# SOCPowerSupplys.net
KiCad netlist of a schematic drawn in Altium Designer
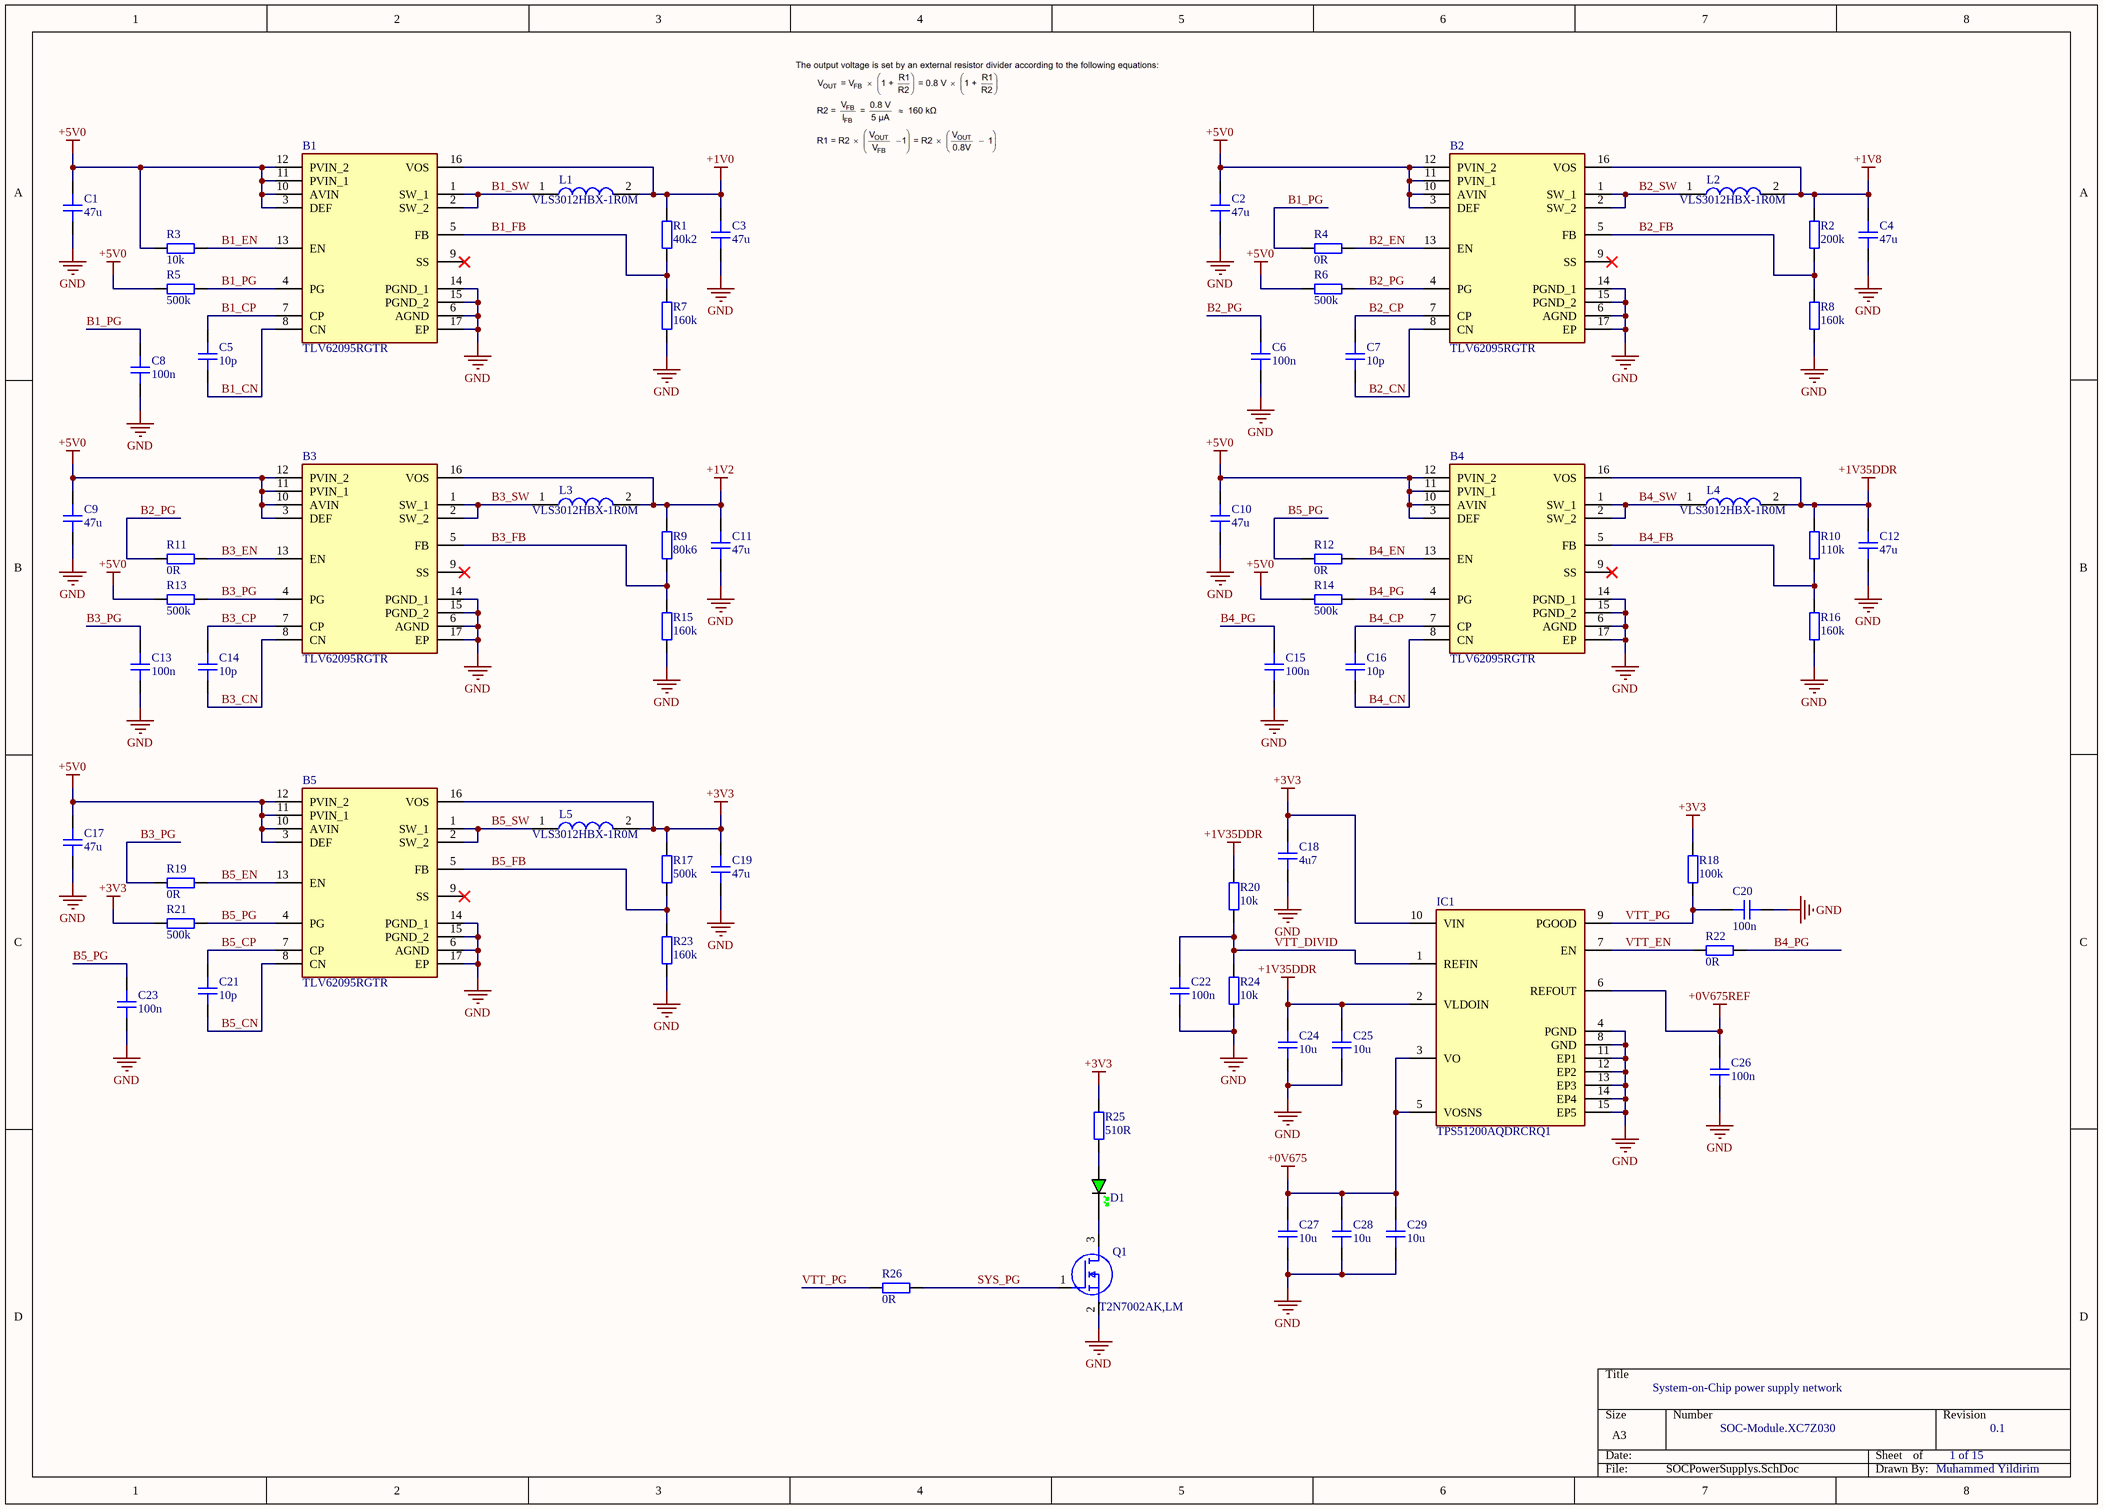
[diagram p0: SOCPowerSupplys.SchDoc]

(export (version "E")
  (design (tool "Eeschema 10.0.6"))
  (components
    (comp (ref "B1")
      (value "TLV62095RGTR")
      (footprint "QFN50P300X300X100-17N-D")
      (description "4A Synchronous Step Down Converter with DCS Control")
      (fields (field (name "MOUSER PART NUMBER") "595-TLV62095RGTR"))
      (libsource (lib "XC7Z030SCHLib") (part "TLV62095RGTR"))
    )
    (comp (ref "B2")
      (value "TLV62095RGTR")
      (footprint "QFN50P300X300X100-17N-D")
      (description "4A Synchronous Step Down Converter with DCS Control")
      (fields (field (name "MOUSER PART NUMBER") "595-TLV62095RGTR"))
      (libsource (lib "XC7Z030SCHLib") (part "TLV62095RGTR"))
    )
    (comp (ref "B3")
      (value "TLV62095RGTR")
      (footprint "QFN50P300X300X100-17N-D")
      (description "4A Synchronous Step Down Converter with DCS Control")
      (fields (field (name "MOUSER PART NUMBER") "595-TLV62095RGTR"))
      (libsource (lib "XC7Z030SCHLib") (part "TLV62095RGTR"))
    )
    (comp (ref "B4")
      (value "TLV62095RGTR")
      (footprint "QFN50P300X300X100-17N-D")
      (description "4A Synchronous Step Down Converter with DCS Control")
      (fields (field (name "MOUSER PART NUMBER") "595-TLV62095RGTR"))
      (libsource (lib "XC7Z030SCHLib") (part "TLV62095RGTR"))
    )
    (comp (ref "B5")
      (value "TLV62095RGTR")
      (footprint "QFN50P300X300X100-17N-D")
      (description "4A Synchronous Step Down Converter with DCS Control")
      (fields (field (name "MOUSER PART NUMBER") "595-TLV62095RGTR"))
      (libsource (lib "XC7Z030SCHLib") (part "TLV62095RGTR"))
    )
    (comp (ref "C1")
      (value "47u")
      (footprint "CAP_0805")
      (description "Capacitor SMD 0805")
      (libsource (lib "Schematic-Lib-PhilsLab") (part "CAP_0805"))
    )
    (comp (ref "C2")
      (value "47u")
      (footprint "CAP_0805")
      (description "Capacitor SMD 0805")
      (libsource (lib "Schematic-Lib-PhilsLab") (part "CAP_0805"))
    )
    (comp (ref "C3")
      (value "47u")
      (footprint "CAP_0805")
      (description "Capacitor SMD 0805")
      (libsource (lib "Schematic-Lib-PhilsLab") (part "CAP_0805"))
    )
    (comp (ref "C4")
      (value "47u")
      (footprint "CAP_0805")
      (description "Capacitor SMD 0805")
      (libsource (lib "Schematic-Lib-PhilsLab") (part "CAP_0805"))
    )
    (comp (ref "C5")
      (value "10p")
      (footprint "CAP_0402")
      (description "Capacitor SMD 0402")
      (libsource (lib "Schematic-Lib-PhilsLab") (part "CAP_0402"))
    )
    (comp (ref "C6")
      (value "100n")
      (footprint "CAP_0402")
      (description "Capacitor SMD 0402")
      (libsource (lib "Schematic-Lib-PhilsLab") (part "CAP_0402"))
    )
    (comp (ref "C7")
      (value "10p")
      (footprint "CAP_0402")
      (description "Capacitor SMD 0402")
      (libsource (lib "Schematic-Lib-PhilsLab") (part "CAP_0402"))
    )
    (comp (ref "C8")
      (value "100n")
      (footprint "CAP_0402")
      (description "Capacitor SMD 0402")
      (libsource (lib "Schematic-Lib-PhilsLab") (part "CAP_0402"))
    )
    (comp (ref "C9")
      (value "47u")
      (footprint "CAP_0805")
      (description "Capacitor SMD 0805")
      (libsource (lib "Schematic-Lib-PhilsLab") (part "CAP_0805"))
    )
    (comp (ref "C10")
      (value "47u")
      (footprint "CAP_0805")
      (description "Capacitor SMD 0805")
      (libsource (lib "Schematic-Lib-PhilsLab") (part "CAP_0805"))
    )
    (comp (ref "C11")
      (value "47u")
      (footprint "CAP_0805")
      (description "Capacitor SMD 0805")
      (libsource (lib "Schematic-Lib-PhilsLab") (part "CAP_0805"))
    )
    (comp (ref "C12")
      (value "47u")
      (footprint "CAP_0805")
      (description "Capacitor SMD 0805")
      (libsource (lib "Schematic-Lib-PhilsLab") (part "CAP_0805"))
    )
    (comp (ref "C13")
      (value "100n")
      (footprint "CAP_0402")
      (description "Capacitor SMD 0402")
      (libsource (lib "Schematic-Lib-PhilsLab") (part "CAP_0402"))
    )
    (comp (ref "C14")
      (value "10p")
      (footprint "CAP_0402")
      (description "Capacitor SMD 0402")
      (libsource (lib "Schematic-Lib-PhilsLab") (part "CAP_0402"))
    )
    (comp (ref "C15")
      (value "100n")
      (footprint "CAP_0402")
      (description "Capacitor SMD 0402")
      (libsource (lib "Schematic-Lib-PhilsLab") (part "CAP_0402"))
    )
    (comp (ref "C16")
      (value "10p")
      (footprint "CAP_0402")
      (description "Capacitor SMD 0402")
      (libsource (lib "Schematic-Lib-PhilsLab") (part "CAP_0402"))
    )
    (comp (ref "C17")
      (value "47u")
      (footprint "CAP_0805")
      (description "Capacitor SMD 0805")
      (libsource (lib "Schematic-Lib-PhilsLab") (part "CAP_0805"))
    )
    (comp (ref "C18")
      (value "4u7")
      (footprint "CAP_0402")
      (description "Capacitor SMD 0402")
      (libsource (lib "Schematic-Lib-PhilsLab") (part "CAP_0402"))
    )
    (comp (ref "C19")
      (value "47u")
      (footprint "CAP_0805")
      (description "Capacitor SMD 0805")
      (libsource (lib "Schematic-Lib-PhilsLab") (part "CAP_0805"))
    )
    (comp (ref "C20")
      (value "100n")
      (footprint "CAP_0402")
      (description "Capacitor SMD 0402")
      (libsource (lib "Schematic-Lib-PhilsLab") (part "CAP_0402"))
    )
    (comp (ref "C21")
      (value "10p")
      (footprint "CAP_0402")
      (description "Capacitor SMD 0402")
      (libsource (lib "Schematic-Lib-PhilsLab") (part "CAP_0402"))
    )
    (comp (ref "C22")
      (value "100n")
      (footprint "CAP_0402")
      (description "Capacitor SMD 0402")
      (libsource (lib "Schematic-Lib-PhilsLab") (part "CAP_0402"))
    )
    (comp (ref "C23")
      (value "100n")
      (footprint "CAP_0402")
      (description "Capacitor SMD 0402")
      (libsource (lib "Schematic-Lib-PhilsLab") (part "CAP_0402"))
    )
    (comp (ref "C24")
      (value "10u")
      (footprint "CAP_0603")
      (description "Capacitor SMD 0603")
      (libsource (lib "Schematic-Lib-PhilsLab") (part "CAP_0603"))
    )
    (comp (ref "C25")
      (value "10u")
      (footprint "CAP_0603")
      (description "Capacitor SMD 0603")
      (libsource (lib "Schematic-Lib-PhilsLab") (part "CAP_0603"))
    )
    (comp (ref "C26")
      (value "100n")
      (footprint "CAP_0402")
      (description "Capacitor SMD 0402")
      (libsource (lib "Schematic-Lib-PhilsLab") (part "CAP_0402"))
    )
    (comp (ref "C27")
      (value "10u")
      (footprint "CAP_0603")
      (description "Capacitor SMD 0603")
      (libsource (lib "Schematic-Lib-PhilsLab") (part "CAP_0603"))
    )
    (comp (ref "C28")
      (value "10u")
      (footprint "CAP_0603")
      (description "Capacitor SMD 0603")
      (libsource (lib "Schematic-Lib-PhilsLab") (part "CAP_0603"))
    )
    (comp (ref "C29")
      (value "10u")
      (footprint "CAP_0603")
      (description "Capacitor SMD 0603")
      (libsource (lib "Schematic-Lib-PhilsLab") (part "CAP_0603"))
    )
    (comp (ref "D1")
      (value "GREEN")
      (footprint "LED_0603_GREEN")
      (description "LED 0603 GREEN SMD")
      (libsource (lib "Schematic-Lib-PhilsLab") (part "LED_0603_GREEN"))
    )
    (comp (ref "IC1")
      (value "TPS51200AQDRCRQ1")
      (footprint "TPS51200AQDRCRQ1")
      (description "Texas Instruments Sink and Source DDR Termination Regulator")
      (libsource (lib "XC7Z030SCHLib") (part "TPS51200AQDRCRQ1"))
    )
    (comp (ref "L1")
      (value "VLS3012HBX-1R0M")
      (footprint "XC7Z030PCBLib:VLS3012")
      (description "Inductor")
      (fields (field (name "MOUSER PART NUMBER") "810-VLS3012HBX-1R0M"))
      (libsource (lib "XC7Z030SCHLib") (part "VLS3012HBX-1R0M"))
    )
    (comp (ref "L2")
      (value "VLS3012HBX-1R0M")
      (footprint "XC7Z030PCBLib:VLS3012")
      (description "Inductor")
      (fields (field (name "MOUSER PART NUMBER") "810-VLS3012HBX-1R0M"))
      (libsource (lib "XC7Z030SCHLib") (part "VLS3012HBX-1R0M"))
    )
    (comp (ref "L3")
      (value "VLS3012HBX-1R0M")
      (footprint "XC7Z030PCBLib:VLS3012")
      (description "Inductor")
      (fields (field (name "MOUSER PART NUMBER") "810-VLS3012HBX-1R0M"))
      (libsource (lib "XC7Z030SCHLib") (part "VLS3012HBX-1R0M"))
    )
    (comp (ref "L4")
      (value "VLS3012HBX-1R0M")
      (footprint "XC7Z030PCBLib:VLS3012")
      (description "Inductor")
      (fields (field (name "MOUSER PART NUMBER") "810-VLS3012HBX-1R0M"))
      (libsource (lib "XC7Z030SCHLib") (part "VLS3012HBX-1R0M"))
    )
    (comp (ref "L5")
      (value "VLS3012HBX-1R0M")
      (footprint "XC7Z030PCBLib:VLS3012")
      (description "Inductor")
      (fields (field (name "MOUSER PART NUMBER") "810-VLS3012HBX-1R0M"))
      (libsource (lib "XC7Z030SCHLib") (part "VLS3012HBX-1R0M"))
    )
    (comp (ref "Q1")
      (value "T2N7002AK,LM")
      (footprint "Footprint-Lib-PhilsLab:TBAT54CLM")
      (description "MOSFET (N-Channel)")
      (fields (field (name "MOUSER PART NUMBER") "757-T2N7002AKLM"))
      (libsource (lib "Schematic-Lib-PhilsLab") (part "T2N7002AK,LM"))
    )
    (comp (ref "R1")
      (value "40k2")
      (footprint "RES_0402")
      (description "Resistor SMD 0402")
      (libsource (lib "Schematic-Lib-PhilsLab") (part "RES_0402"))
    )
    (comp (ref "R2")
      (value "200k")
      (footprint "RES_0402")
      (description "Resistor SMD 0402")
      (libsource (lib "Schematic-Lib-PhilsLab") (part "RES_0402"))
    )
    (comp (ref "R3")
      (value "10k")
      (footprint "RES_0402")
      (description "Resistor SMD 0402")
      (libsource (lib "Schematic-Lib-PhilsLab") (part "RES_0402"))
    )
    (comp (ref "R4")
      (value "0R")
      (footprint "RES_0402")
      (description "Resistor SMD 0402")
      (libsource (lib "Schematic-Lib-PhilsLab") (part "RES_0402"))
    )
    (comp (ref "R5")
      (value "500k")
      (footprint "RES_0402")
      (description "Resistor SMD 0402")
      (libsource (lib "Schematic-Lib-PhilsLab") (part "RES_0402"))
    )
    (comp (ref "R6")
      (value "500k")
      (footprint "RES_0402")
      (description "Resistor SMD 0402")
      (libsource (lib "Schematic-Lib-PhilsLab") (part "RES_0402"))
    )
    (comp (ref "R7")
      (value "160k")
      (footprint "RES_0402")
      (description "Resistor SMD 0402")
      (libsource (lib "Schematic-Lib-PhilsLab") (part "RES_0402"))
    )
    (comp (ref "R8")
      (value "160k")
      (footprint "RES_0402")
      (description "Resistor SMD 0402")
      (libsource (lib "Schematic-Lib-PhilsLab") (part "RES_0402"))
    )
    (comp (ref "R9")
      (value "80k6")
      (footprint "RES_0402")
      (description "Resistor SMD 0402")
      (libsource (lib "Schematic-Lib-PhilsLab") (part "RES_0402"))
    )
    (comp (ref "R10")
      (value "110k")
      (footprint "RES_0402")
      (description "Resistor SMD 0402")
      (libsource (lib "Schematic-Lib-PhilsLab") (part "RES_0402"))
    )
    (comp (ref "R11")
      (value "0R")
      (footprint "RES_0402")
      (description "Resistor SMD 0402")
      (libsource (lib "Schematic-Lib-PhilsLab") (part "RES_0402"))
    )
    (comp (ref "R12")
      (value "0R")
      (footprint "RES_0402")
      (description "Resistor SMD 0402")
      (libsource (lib "Schematic-Lib-PhilsLab") (part "RES_0402"))
    )
    (comp (ref "R13")
      (value "500k")
      (footprint "RES_0402")
      (description "Resistor SMD 0402")
      (libsource (lib "Schematic-Lib-PhilsLab") (part "RES_0402"))
    )
    (comp (ref "R14")
      (value "500k")
      (footprint "RES_0402")
      (description "Resistor SMD 0402")
      (libsource (lib "Schematic-Lib-PhilsLab") (part "RES_0402"))
    )
    (comp (ref "R15")
      (value "160k")
      (footprint "RES_0402")
      (description "Resistor SMD 0402")
      (libsource (lib "Schematic-Lib-PhilsLab") (part "RES_0402"))
    )
    (comp (ref "R16")
      (value "160k")
      (footprint "RES_0402")
      (description "Resistor SMD 0402")
      (libsource (lib "Schematic-Lib-PhilsLab") (part "RES_0402"))
    )
    (comp (ref "R17")
      (value "500k")
      (footprint "RES_0402")
      (description "Resistor SMD 0402")
      (libsource (lib "Schematic-Lib-PhilsLab") (part "RES_0402"))
    )
    (comp (ref "R18")
      (value "100k")
      (footprint "RES_0402")
      (description "Resistor SMD 0402")
      (libsource (lib "Schematic-Lib-PhilsLab") (part "RES_0402"))
    )
    (comp (ref "R19")
      (value "0R")
      (footprint "RES_0402")
      (description "Resistor SMD 0402")
      (libsource (lib "Schematic-Lib-PhilsLab") (part "RES_0402"))
    )
    (comp (ref "R20")
      (value "10k")
      (footprint "RES_0402")
      (description "Resistor SMD 0402")
      (libsource (lib "Schematic-Lib-PhilsLab") (part "RES_0402"))
    )
    (comp (ref "R21")
      (value "500k")
      (footprint "RES_0402")
      (description "Resistor SMD 0402")
      (libsource (lib "Schematic-Lib-PhilsLab") (part "RES_0402"))
    )
    (comp (ref "R22")
      (value "0R")
      (footprint "RES_0402")
      (description "Resistor SMD 0402")
      (libsource (lib "Schematic-Lib-PhilsLab") (part "RES_0402"))
    )
    (comp (ref "R23")
      (value "160k")
      (footprint "RES_0402")
      (description "Resistor SMD 0402")
      (libsource (lib "Schematic-Lib-PhilsLab") (part "RES_0402"))
    )
    (comp (ref "R24")
      (value "10k")
      (footprint "RES_0402")
      (description "Resistor SMD 0402")
      (libsource (lib "Schematic-Lib-PhilsLab") (part "RES_0402"))
    )
    (comp (ref "R25")
      (value "510R")
      (footprint "RES_0603")
      (description "Resistor SMD 0603")
      (libsource (lib "Schematic-Lib-PhilsLab") (part "RES_0603"))
    )
    (comp (ref "R26")
      (value "0R")
      (footprint "RES_0402")
      (description "Resistor SMD 0402")
      (libsource (lib "Schematic-Lib-PhilsLab") (part "RES_0402"))
    )
  )
  (nets
    (net (code "1") (name "+0V675") (class "Default")
      (node (ref "C27") (pin "2") (pinfunction "2_2") (pintype "passive"))
      (node (ref "C28") (pin "2") (pinfunction "2_2") (pintype "passive"))
      (node (ref "C29") (pin "2") (pinfunction "2_2") (pintype "passive"))
      (node (ref "IC1") (pin "3") (pinfunction "VO_3") (pintype "passive"))
      (node (ref "IC1") (pin "5") (pinfunction "VOSNS_5") (pintype "passive"))
    )
    (net (code "2") (name "+0V675REF") (class "Default")
      (node (ref "C26") (pin "2") (pinfunction "2_2") (pintype "passive"))
      (node (ref "IC1") (pin "6") (pinfunction "REFOUT_6") (pintype "passive"))
    )
    (net (code "3") (name "+1V0") (class "Default")
      (node (ref "B1") (pin "16") (pinfunction "VOS_16") (pintype "passive"))
      (node (ref "C3") (pin "2") (pinfunction "2_2") (pintype "passive"))
      (node (ref "L1") (pin "2") (pinfunction "2_2") (pintype "passive"))
      (node (ref "R1") (pin "2") (pinfunction "2_2") (pintype "passive"))
    )
    (net (code "4") (name "+1V2") (class "Default")
      (node (ref "B3") (pin "16") (pinfunction "VOS_16") (pintype "passive"))
      (node (ref "C11") (pin "2") (pinfunction "2_2") (pintype "passive"))
      (node (ref "L3") (pin "2") (pinfunction "2_2") (pintype "passive"))
      (node (ref "R9") (pin "2") (pinfunction "2_2") (pintype "passive"))
    )
    (net (code "5") (name "+1V8") (class "Default")
      (node (ref "B2") (pin "16") (pinfunction "VOS_16") (pintype "passive"))
      (node (ref "C4") (pin "2") (pinfunction "2_2") (pintype "passive"))
      (node (ref "L2") (pin "2") (pinfunction "2_2") (pintype "passive"))
      (node (ref "R2") (pin "2") (pinfunction "2_2") (pintype "passive"))
    )
    (net (code "6") (name "+1V35DDR") (class "Default")
      (node (ref "B4") (pin "16") (pinfunction "VOS_16") (pintype "passive"))
      (node (ref "C12") (pin "2") (pinfunction "2_2") (pintype "passive"))
      (node (ref "C24") (pin "2") (pinfunction "2_2") (pintype "passive"))
      (node (ref "C25") (pin "2") (pinfunction "2_2") (pintype "passive"))
      (node (ref "IC1") (pin "2") (pinfunction "VLDOIN_2") (pintype "passive"))
      (node (ref "L4") (pin "2") (pinfunction "2_2") (pintype "passive"))
      (node (ref "R10") (pin "2") (pinfunction "2_2") (pintype "passive"))
      (node (ref "R20") (pin "2") (pinfunction "2_2") (pintype "passive"))
    )
    (net (code "7") (name "+3V3") (class "Default")
      (node (ref "B5") (pin "16") (pinfunction "VOS_16") (pintype "passive"))
      (node (ref "C18") (pin "2") (pinfunction "2_2") (pintype "passive"))
      (node (ref "C19") (pin "2") (pinfunction "2_2") (pintype "passive"))
      (node (ref "IC1") (pin "10") (pinfunction "VIN_10") (pintype "passive"))
      (node (ref "L5") (pin "2") (pinfunction "2_2") (pintype "passive"))
      (node (ref "R17") (pin "2") (pinfunction "2_2") (pintype "passive"))
      (node (ref "R18") (pin "2") (pinfunction "2_2") (pintype "passive"))
      (node (ref "R21") (pin "1") (pinfunction "1_1") (pintype "passive"))
      (node (ref "R25") (pin "2") (pinfunction "2_2") (pintype "passive"))
    )
    (net (code "8") (name "+5V0") (class "Default")
      (node (ref "B1") (pin "10") (pinfunction "AVIN_10") (pintype "passive"))
      (node (ref "B1") (pin "11") (pinfunction "PVIN_1_11") (pintype "passive"))
      (node (ref "B1") (pin "12") (pinfunction "PVIN_2_12") (pintype "passive"))
      (node (ref "B1") (pin "3") (pinfunction "DEF_3") (pintype "passive"))
      (node (ref "B2") (pin "10") (pinfunction "AVIN_10") (pintype "passive"))
      (node (ref "B2") (pin "11") (pinfunction "PVIN_1_11") (pintype "passive"))
      (node (ref "B2") (pin "12") (pinfunction "PVIN_2_12") (pintype "passive"))
      (node (ref "B2") (pin "3") (pinfunction "DEF_3") (pintype "passive"))
      (node (ref "B3") (pin "10") (pinfunction "AVIN_10") (pintype "passive"))
      (node (ref "B3") (pin "11") (pinfunction "PVIN_1_11") (pintype "passive"))
      (node (ref "B3") (pin "12") (pinfunction "PVIN_2_12") (pintype "passive"))
      (node (ref "B3") (pin "3") (pinfunction "DEF_3") (pintype "passive"))
      (node (ref "B4") (pin "10") (pinfunction "AVIN_10") (pintype "passive"))
      (node (ref "B4") (pin "11") (pinfunction "PVIN_1_11") (pintype "passive"))
      (node (ref "B4") (pin "12") (pinfunction "PVIN_2_12") (pintype "passive"))
      (node (ref "B4") (pin "3") (pinfunction "DEF_3") (pintype "passive"))
      (node (ref "B5") (pin "10") (pinfunction "AVIN_10") (pintype "passive"))
      (node (ref "B5") (pin "11") (pinfunction "PVIN_1_11") (pintype "passive"))
      (node (ref "B5") (pin "12") (pinfunction "PVIN_2_12") (pintype "passive"))
      (node (ref "B5") (pin "3") (pinfunction "DEF_3") (pintype "passive"))
      (node (ref "C1") (pin "2") (pinfunction "2_2") (pintype "passive"))
      (node (ref "C10") (pin "2") (pinfunction "2_2") (pintype "passive"))
      (node (ref "C17") (pin "2") (pinfunction "2_2") (pintype "passive"))
      (node (ref "C2") (pin "2") (pinfunction "2_2") (pintype "passive"))
      (node (ref "C9") (pin "2") (pinfunction "2_2") (pintype "passive"))
      (node (ref "R13") (pin "1") (pinfunction "1_1") (pintype "passive"))
      (node (ref "R14") (pin "1") (pinfunction "1_1") (pintype "passive"))
      (node (ref "R3") (pin "1") (pinfunction "1_1") (pintype "passive"))
      (node (ref "R5") (pin "1") (pinfunction "1_1") (pintype "passive"))
      (node (ref "R6") (pin "1") (pinfunction "1_1") (pintype "passive"))
    )
    (net (code "9") (name "/B1_CN") (class "Default")
      (node (ref "B1") (pin "8") (pinfunction "CN_8") (pintype "passive"))
      (node (ref "C5") (pin "1") (pinfunction "1_1") (pintype "passive"))
    )
    (net (code "10") (name "/B1_CP") (class "Default")
      (node (ref "B1") (pin "7") (pinfunction "CP_7") (pintype "passive"))
      (node (ref "C5") (pin "2") (pinfunction "2_2") (pintype "passive"))
    )
    (net (code "11") (name "/B1_EN") (class "Default")
      (node (ref "B1") (pin "13") (pinfunction "EN_13") (pintype "passive"))
      (node (ref "R3") (pin "2") (pinfunction "2_2") (pintype "passive"))
    )
    (net (code "12") (name "/B1_FB") (class "Default")
      (node (ref "B1") (pin "5") (pinfunction "FB_5") (pintype "passive"))
      (node (ref "R1") (pin "1") (pinfunction "1_1") (pintype "passive"))
      (node (ref "R7") (pin "2") (pinfunction "2_2") (pintype "passive"))
    )
    (net (code "13") (name "/B1_PG") (class "Default")
      (node (ref "B1") (pin "4") (pinfunction "PG_4") (pintype "passive"))
      (node (ref "C8") (pin "2") (pinfunction "2_2") (pintype "passive"))
      (node (ref "R4") (pin "2") (pinfunction "2_2") (pintype "passive"))
      (node (ref "R5") (pin "2") (pinfunction "2_2") (pintype "passive"))
    )
    (net (code "14") (name "/B1_SW") (class "Default")
      (node (ref "B1") (pin "1") (pinfunction "SW_1_1") (pintype "passive"))
      (node (ref "B1") (pin "2") (pinfunction "SW_2_2") (pintype "passive"))
      (node (ref "L1") (pin "1") (pinfunction "1_1") (pintype "passive"))
    )
    (net (code "15") (name "/B2_CN") (class "Default")
      (node (ref "B2") (pin "8") (pinfunction "CN_8") (pintype "passive"))
      (node (ref "C7") (pin "1") (pinfunction "1_1") (pintype "passive"))
    )
    (net (code "16") (name "/B2_CP") (class "Default")
      (node (ref "B2") (pin "7") (pinfunction "CP_7") (pintype "passive"))
      (node (ref "C7") (pin "2") (pinfunction "2_2") (pintype "passive"))
    )
    (net (code "17") (name "/B2_EN") (class "Default")
      (node (ref "B2") (pin "13") (pinfunction "EN_13") (pintype "passive"))
      (node (ref "R4") (pin "1") (pinfunction "1_1") (pintype "passive"))
    )
    (net (code "18") (name "/B2_FB") (class "Default")
      (node (ref "B2") (pin "5") (pinfunction "FB_5") (pintype "passive"))
      (node (ref "R2") (pin "1") (pinfunction "1_1") (pintype "passive"))
      (node (ref "R8") (pin "2") (pinfunction "2_2") (pintype "passive"))
    )
    (net (code "19") (name "/B2_PG") (class "Default")
      (node (ref "B2") (pin "4") (pinfunction "PG_4") (pintype "passive"))
      (node (ref "C6") (pin "2") (pinfunction "2_2") (pintype "passive"))
      (node (ref "R11") (pin "2") (pinfunction "2_2") (pintype "passive"))
      (node (ref "R6") (pin "2") (pinfunction "2_2") (pintype "passive"))
    )
    (net (code "20") (name "/B2_SW") (class "Default")
      (node (ref "B2") (pin "1") (pinfunction "SW_1_1") (pintype "passive"))
      (node (ref "B2") (pin "2") (pinfunction "SW_2_2") (pintype "passive"))
      (node (ref "L2") (pin "1") (pinfunction "1_1") (pintype "passive"))
    )
    (net (code "21") (name "/B3_CN") (class "Default")
      (node (ref "B3") (pin "8") (pinfunction "CN_8") (pintype "passive"))
      (node (ref "C14") (pin "1") (pinfunction "1_1") (pintype "passive"))
    )
    (net (code "22") (name "/B3_CP") (class "Default")
      (node (ref "B3") (pin "7") (pinfunction "CP_7") (pintype "passive"))
      (node (ref "C14") (pin "2") (pinfunction "2_2") (pintype "passive"))
    )
    (net (code "23") (name "/B3_EN") (class "Default")
      (node (ref "B3") (pin "13") (pinfunction "EN_13") (pintype "passive"))
      (node (ref "R11") (pin "1") (pinfunction "1_1") (pintype "passive"))
    )
    (net (code "24") (name "/B3_FB") (class "Default")
      (node (ref "B3") (pin "5") (pinfunction "FB_5") (pintype "passive"))
      (node (ref "R15") (pin "2") (pinfunction "2_2") (pintype "passive"))
      (node (ref "R9") (pin "1") (pinfunction "1_1") (pintype "passive"))
    )
    (net (code "25") (name "/B3_PG") (class "Default")
      (node (ref "B3") (pin "4") (pinfunction "PG_4") (pintype "passive"))
      (node (ref "C13") (pin "2") (pinfunction "2_2") (pintype "passive"))
      (node (ref "R13") (pin "2") (pinfunction "2_2") (pintype "passive"))
      (node (ref "R19") (pin "2") (pinfunction "2_2") (pintype "passive"))
    )
    (net (code "26") (name "/B3_SW") (class "Default")
      (node (ref "B3") (pin "1") (pinfunction "SW_1_1") (pintype "passive"))
      (node (ref "B3") (pin "2") (pinfunction "SW_2_2") (pintype "passive"))
      (node (ref "L3") (pin "1") (pinfunction "1_1") (pintype "passive"))
    )
    (net (code "27") (name "/B4_CN") (class "Default")
      (node (ref "B4") (pin "8") (pinfunction "CN_8") (pintype "passive"))
      (node (ref "C16") (pin "1") (pinfunction "1_1") (pintype "passive"))
    )
    (net (code "28") (name "/B4_CP") (class "Default")
      (node (ref "B4") (pin "7") (pinfunction "CP_7") (pintype "passive"))
      (node (ref "C16") (pin "2") (pinfunction "2_2") (pintype "passive"))
    )
    (net (code "29") (name "/B4_EN") (class "Default")
      (node (ref "B4") (pin "13") (pinfunction "EN_13") (pintype "passive"))
      (node (ref "R12") (pin "1") (pinfunction "1_1") (pintype "passive"))
    )
    (net (code "30") (name "/B4_FB") (class "Default")
      (node (ref "B4") (pin "5") (pinfunction "FB_5") (pintype "passive"))
      (node (ref "R10") (pin "1") (pinfunction "1_1") (pintype "passive"))
      (node (ref "R16") (pin "2") (pinfunction "2_2") (pintype "passive"))
    )
    (net (code "31") (name "/B4_PG") (class "Default")
      (node (ref "B4") (pin "4") (pinfunction "PG_4") (pintype "passive"))
      (node (ref "C15") (pin "2") (pinfunction "2_2") (pintype "passive"))
      (node (ref "R14") (pin "2") (pinfunction "2_2") (pintype "passive"))
      (node (ref "R22") (pin "1") (pinfunction "1_1") (pintype "passive"))
    )
    (net (code "32") (name "/B4_SW") (class "Default")
      (node (ref "B4") (pin "1") (pinfunction "SW_1_1") (pintype "passive"))
      (node (ref "B4") (pin "2") (pinfunction "SW_2_2") (pintype "passive"))
      (node (ref "L4") (pin "1") (pinfunction "1_1") (pintype "passive"))
    )
    (net (code "33") (name "/B5_CN") (class "Default")
      (node (ref "B5") (pin "8") (pinfunction "CN_8") (pintype "passive"))
      (node (ref "C21") (pin "1") (pinfunction "1_1") (pintype "passive"))
    )
    (net (code "34") (name "/B5_CP") (class "Default")
      (node (ref "B5") (pin "7") (pinfunction "CP_7") (pintype "passive"))
      (node (ref "C21") (pin "2") (pinfunction "2_2") (pintype "passive"))
    )
    (net (code "35") (name "/B5_EN") (class "Default")
      (node (ref "B5") (pin "13") (pinfunction "EN_13") (pintype "passive"))
      (node (ref "R19") (pin "1") (pinfunction "1_1") (pintype "passive"))
    )
    (net (code "36") (name "/B5_FB") (class "Default")
      (node (ref "B5") (pin "5") (pinfunction "FB_5") (pintype "passive"))
      (node (ref "R17") (pin "1") (pinfunction "1_1") (pintype "passive"))
      (node (ref "R23") (pin "2") (pinfunction "2_2") (pintype "passive"))
    )
    (net (code "37") (name "/B5_PG") (class "Default")
      (node (ref "B5") (pin "4") (pinfunction "PG_4") (pintype "passive"))
      (node (ref "C23") (pin "2") (pinfunction "2_2") (pintype "passive"))
      (node (ref "R12") (pin "2") (pinfunction "2_2") (pintype "passive"))
      (node (ref "R21") (pin "2") (pinfunction "2_2") (pintype "passive"))
    )
    (net (code "38") (name "/B5_SW") (class "Default")
      (node (ref "B5") (pin "1") (pinfunction "SW_1_1") (pintype "passive"))
      (node (ref "B5") (pin "2") (pinfunction "SW_2_2") (pintype "passive"))
      (node (ref "L5") (pin "1") (pinfunction "1_1") (pintype "passive"))
    )
    (net (code "39") (name "/SYS_PG") (class "Default")
      (node (ref "Q1") (pin "1") (pinfunction "G_1") (pintype "passive"))
      (node (ref "R26") (pin "1") (pinfunction "1_1") (pintype "passive"))
    )
    (net (code "40") (name "/VTT_DIVID") (class "Default")
      (node (ref "C22") (pin "2") (pinfunction "2_2") (pintype "passive"))
      (node (ref "IC1") (pin "1") (pinfunction "REFIN_1") (pintype "passive"))
      (node (ref "R20") (pin "1") (pinfunction "1_1") (pintype "passive"))
      (node (ref "R24") (pin "2") (pinfunction "2_2") (pintype "passive"))
    )
    (net (code "41") (name "/VTT_EN") (class "Default")
      (node (ref "IC1") (pin "7") (pinfunction "EN_7") (pintype "passive"))
      (node (ref "R22") (pin "2") (pinfunction "2_2") (pintype "passive"))
    )
    (net (code "42") (name "/VTT_PG") (class "Default")
      (node (ref "C20") (pin "2") (pinfunction "2_2") (pintype "passive"))
      (node (ref "IC1") (pin "9") (pinfunction "PGOOD_9") (pintype "passive"))
      (node (ref "R18") (pin "1") (pinfunction "1_1") (pintype "passive"))
      (node (ref "R26") (pin "2") (pinfunction "2_2") (pintype "passive"))
    )
    (net (code "43") (name "GND") (class "Default")
      (node (ref "B1") (pin "14") (pinfunction "PGND_1_14") (pintype "passive"))
      (node (ref "B1") (pin "15") (pinfunction "PGND_2_15") (pintype "passive"))
      (node (ref "B1") (pin "17") (pinfunction "EP_17") (pintype "passive"))
      (node (ref "B1") (pin "6") (pinfunction "AGND_6") (pintype "passive"))
      (node (ref "B2") (pin "14") (pinfunction "PGND_1_14") (pintype "passive"))
      (node (ref "B2") (pin "15") (pinfunction "PGND_2_15") (pintype "passive"))
      (node (ref "B2") (pin "17") (pinfunction "EP_17") (pintype "passive"))
      (node (ref "B2") (pin "6") (pinfunction "AGND_6") (pintype "passive"))
      (node (ref "B3") (pin "14") (pinfunction "PGND_1_14") (pintype "passive"))
      (node (ref "B3") (pin "15") (pinfunction "PGND_2_15") (pintype "passive"))
      (node (ref "B3") (pin "17") (pinfunction "EP_17") (pintype "passive"))
      (node (ref "B3") (pin "6") (pinfunction "AGND_6") (pintype "passive"))
      (node (ref "B4") (pin "14") (pinfunction "PGND_1_14") (pintype "passive"))
      (node (ref "B4") (pin "15") (pinfunction "PGND_2_15") (pintype "passive"))
      (node (ref "B4") (pin "17") (pinfunction "EP_17") (pintype "passive"))
      (node (ref "B4") (pin "6") (pinfunction "AGND_6") (pintype "passive"))
      (node (ref "B5") (pin "14") (pinfunction "PGND_1_14") (pintype "passive"))
      (node (ref "B5") (pin "15") (pinfunction "PGND_2_15") (pintype "passive"))
      (node (ref "B5") (pin "17") (pinfunction "EP_17") (pintype "passive"))
      (node (ref "B5") (pin "6") (pinfunction "AGND_6") (pintype "passive"))
      (node (ref "C1") (pin "1") (pinfunction "1_1") (pintype "passive"))
      (node (ref "C10") (pin "1") (pinfunction "1_1") (pintype "passive"))
      (node (ref "C11") (pin "1") (pinfunction "1_1") (pintype "passive"))
      (node (ref "C12") (pin "1") (pinfunction "1_1") (pintype "passive"))
      (node (ref "C13") (pin "1") (pinfunction "1_1") (pintype "passive"))
      (node (ref "C15") (pin "1") (pinfunction "1_1") (pintype "passive"))
      (node (ref "C17") (pin "1") (pinfunction "1_1") (pintype "passive"))
      (node (ref "C18") (pin "1") (pinfunction "1_1") (pintype "passive"))
      (node (ref "C19") (pin "1") (pinfunction "1_1") (pintype "passive"))
      (node (ref "C2") (pin "1") (pinfunction "1_1") (pintype "passive"))
      (node (ref "C20") (pin "1") (pinfunction "1_1") (pintype "passive"))
      (node (ref "C22") (pin "1") (pinfunction "1_1") (pintype "passive"))
      (node (ref "C23") (pin "1") (pinfunction "1_1") (pintype "passive"))
      (node (ref "C24") (pin "1") (pinfunction "1_1") (pintype "passive"))
      (node (ref "C25") (pin "1") (pinfunction "1_1") (pintype "passive"))
      (node (ref "C26") (pin "1") (pinfunction "1_1") (pintype "passive"))
      (node (ref "C27") (pin "1") (pinfunction "1_1") (pintype "passive"))
      (node (ref "C28") (pin "1") (pinfunction "1_1") (pintype "passive"))
      (node (ref "C29") (pin "1") (pinfunction "1_1") (pintype "passive"))
      (node (ref "C3") (pin "1") (pinfunction "1_1") (pintype "passive"))
      (node (ref "C4") (pin "1") (pinfunction "1_1") (pintype "passive"))
      (node (ref "C6") (pin "1") (pinfunction "1_1") (pintype "passive"))
      (node (ref "C8") (pin "1") (pinfunction "1_1") (pintype "passive"))
      (node (ref "C9") (pin "1") (pinfunction "1_1") (pintype "passive"))
      (node (ref "IC1") (pin "11") (pinfunction "EP1_11") (pintype "passive"))
      (node (ref "IC1") (pin "12") (pinfunction "EP2_12") (pintype "passive"))
      (node (ref "IC1") (pin "13") (pinfunction "EP3_13") (pintype "passive"))
      (node (ref "IC1") (pin "14") (pinfunction "EP4_14") (pintype "passive"))
      (node (ref "IC1") (pin "15") (pinfunction "EP5_15") (pintype "passive"))
      (node (ref "IC1") (pin "4") (pinfunction "PGND_4") (pintype "passive"))
      (node (ref "IC1") (pin "8") (pinfunction "GND_8") (pintype "passive"))
      (node (ref "Q1") (pin "2") (pinfunction "S_2") (pintype "passive"))
      (node (ref "R15") (pin "1") (pinfunction "1_1") (pintype "passive"))
      (node (ref "R16") (pin "1") (pinfunction "1_1") (pintype "passive"))
      (node (ref "R23") (pin "1") (pinfunction "1_1") (pintype "passive"))
      (node (ref "R24") (pin "1") (pinfunction "1_1") (pintype "passive"))
      (node (ref "R7") (pin "1") (pinfunction "1_1") (pintype "passive"))
      (node (ref "R8") (pin "1") (pinfunction "1_1") (pintype "passive"))
    )
    (net (code "44") (name "Net-(D1-PadA)") (class "Default")
      (node (ref "D1") (pin "A") (pinfunction "A_A") (pintype "passive"))
      (node (ref "R25") (pin "1") (pinfunction "1_1") (pintype "passive"))
    )
    (net (code "45") (name "Net-(Q1-D)") (class "Default")
      (node (ref "D1") (pin "K") (pinfunction "K_K") (pintype "passive"))
      (node (ref "Q1") (pin "3") (pinfunction "D_3") (pintype "passive"))
    )
    (net (code "46") (name "unconnected-(B1-SS-Pad9)") (class "Default")
      (node (ref "B1") (pin "9") (pinfunction "SS_9") (pintype "passive+no_connect"))
    )
    (net (code "47") (name "unconnected-(B2-SS-Pad9)") (class "Default")
      (node (ref "B2") (pin "9") (pinfunction "SS_9") (pintype "passive+no_connect"))
    )
    (net (code "48") (name "unconnected-(B3-SS-Pad9)") (class "Default")
      (node (ref "B3") (pin "9") (pinfunction "SS_9") (pintype "passive+no_connect"))
    )
    (net (code "49") (name "unconnected-(B4-SS-Pad9)") (class "Default")
      (node (ref "B4") (pin "9") (pinfunction "SS_9") (pintype "passive+no_connect"))
    )
    (net (code "50") (name "unconnected-(B5-SS-Pad9)") (class "Default")
      (node (ref "B5") (pin "9") (pinfunction "SS_9") (pintype "passive+no_connect"))
    )
  )
)
